# main.net
KiCad netlist of a schematic drawn in Altium Designer
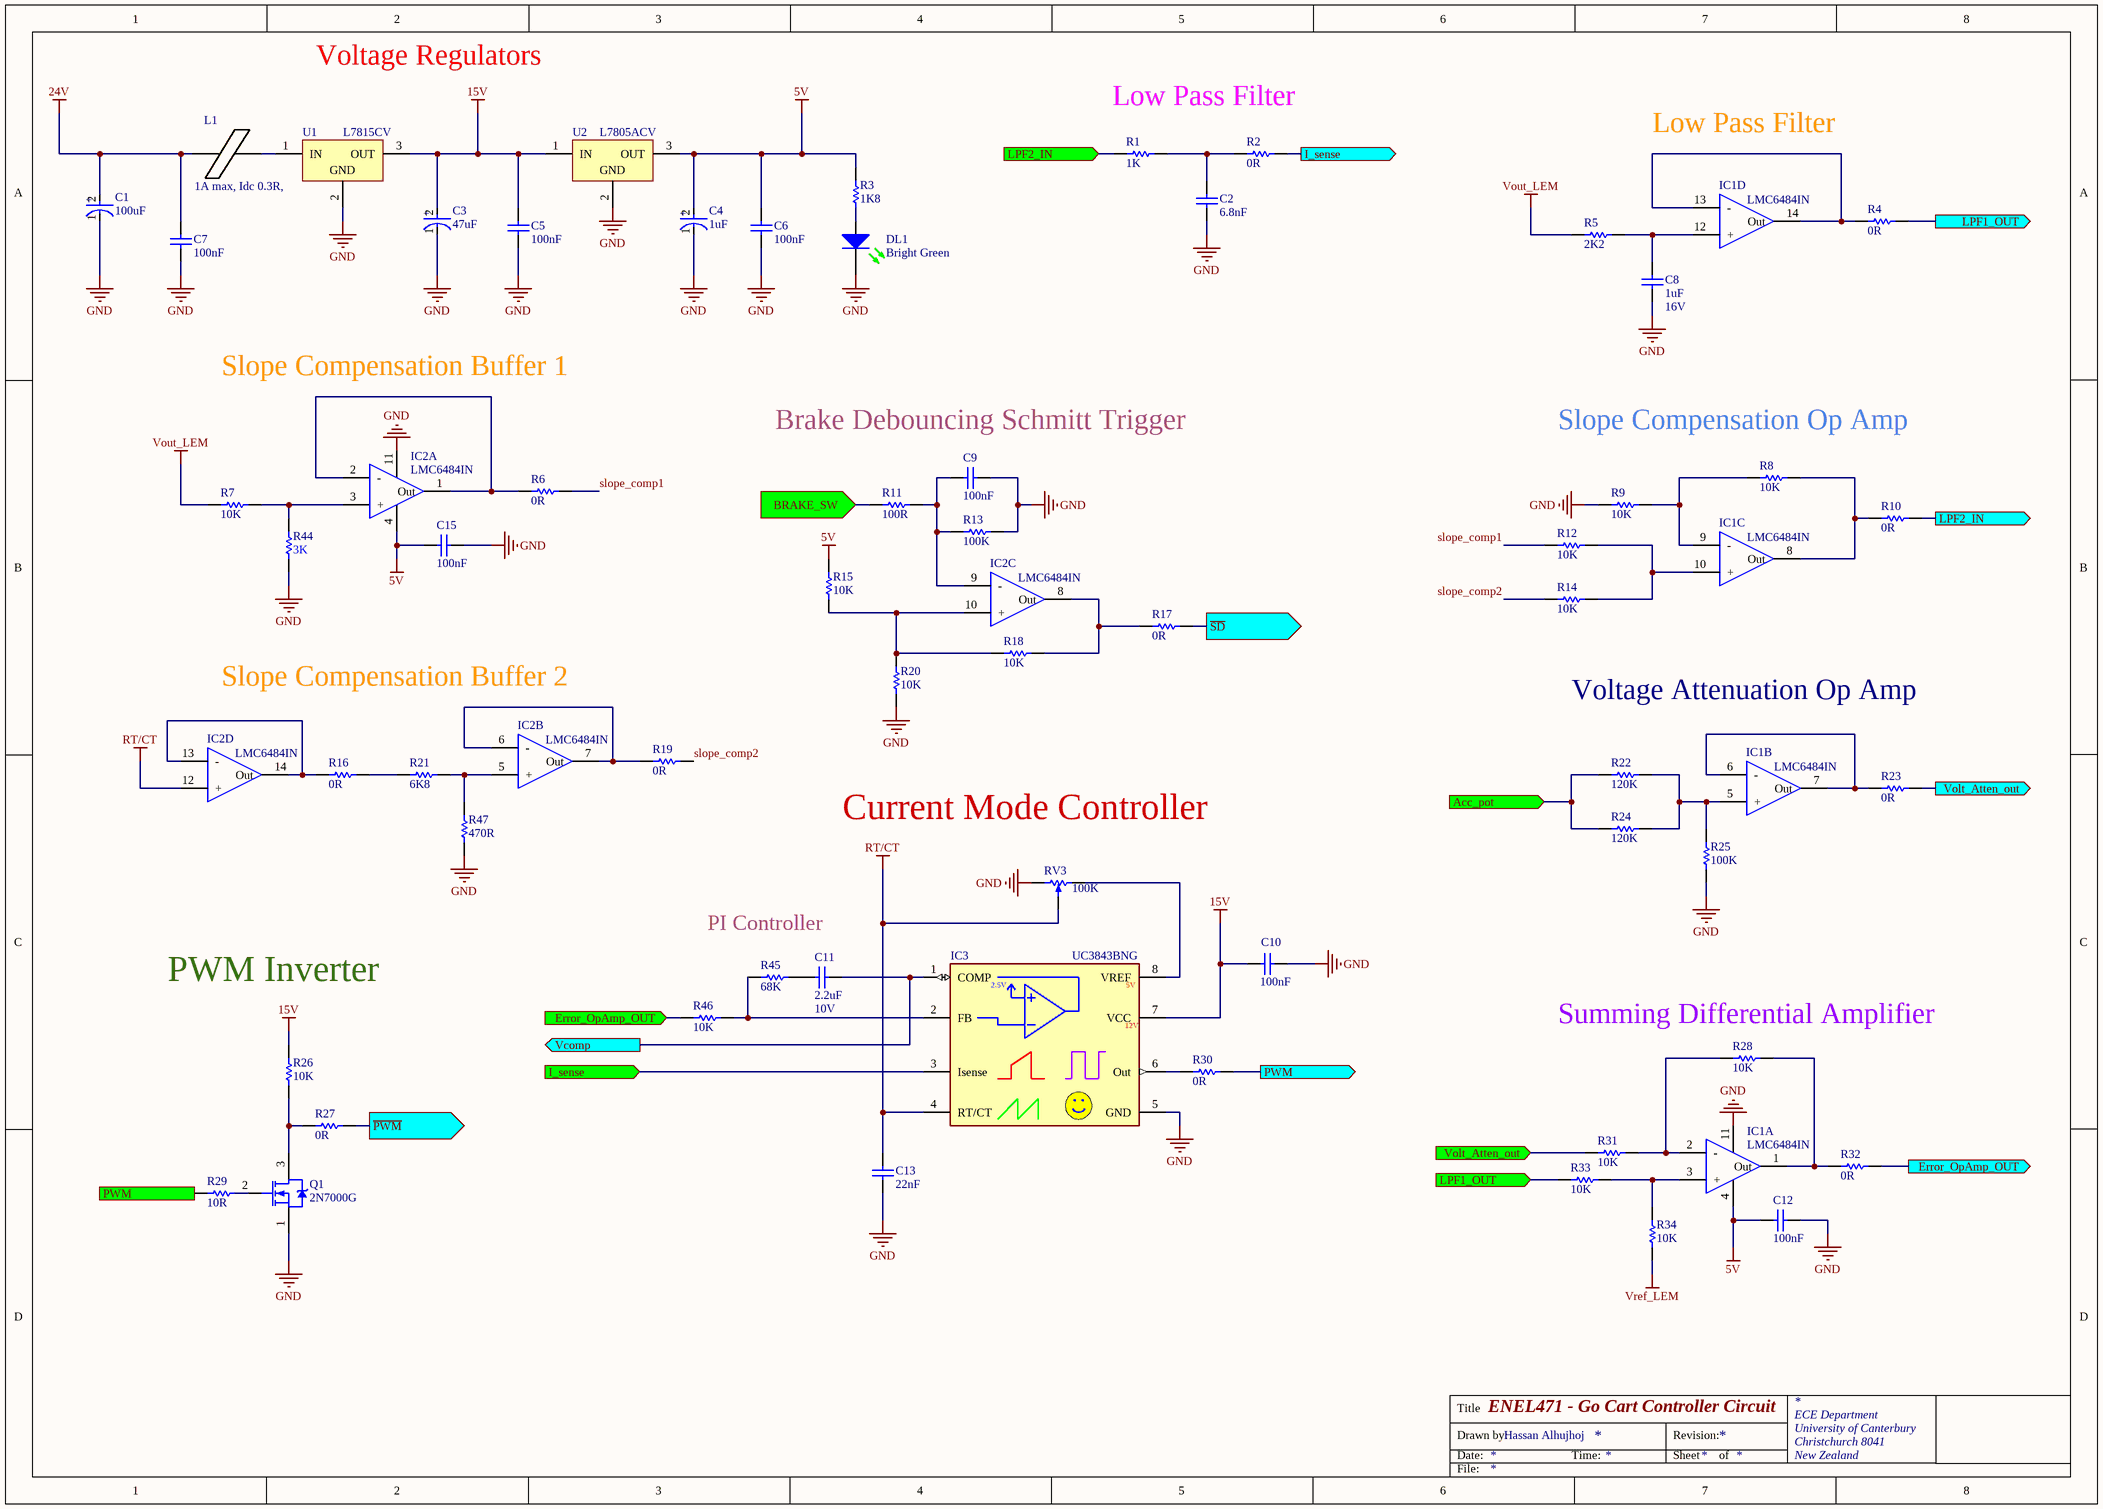
[diagram p0: main.SchDoc]

(export (version "E")
  (design (tool "Eeschema 10.0.6"))
  (components
    (comp (ref "C1")
      (value "100uF")
      (footprint "FP-ESLGM-MFG")
      (description "CAP ALUM 100UF 20% 50V THRU HOLE. Part Number: ESL107M050AGMAA. Dia: 8mm.")
      (fields
        (field (name "TOLERANCE") "20%")
        (field (name "OCTOPART") "https://octopart.com/esl107m050agmaa-kemet-84758890")
      )
      (libsource (lib "Altium Content Vault") (part "a00bbbee19879c290e62620ae7e47b1"))
    )
    (comp (ref "C2")
      (value "6.8nF")
      (footprint "CAPC1608L")
      (description "CAP CER 6.8nF X7R +-10% 50V 0603")
      (libsource (lib "ECE AD19Components_19V1") (part "CC_6.8nF_0603"))
    )
    (comp (ref "C3")
      (value "47uF")
      (footprint "FP-ESLE3-MFG")
      (description "CAP ALUM 10UF 20% 100V THRU HOLE. Part Number: ESL106M100AE3AA. Dia: 6.3mm.")
      (fields (field (name "TOLERANCE") "20%") (field (name "MANUFACTURER PART NUMBER") "ESL106M100AE3AA"))
      (libsource (lib "Altium Content Vault") (part "cf48714ba7e38822c1575c7ec0b6d1f"))
    )
    (comp (ref "C4")
      (value "1uF")
      (footprint "FP-UPW1E220MDD-MFG")
      (description "CAP ALUM 22UF 20% 25V RADIAL. Part Number: UPW1E220MDD. Dia: 5mm.")
      (fields
        (field (name "OCTOPART") "https://octopart.com/upw1e220mdd-nichicon-202818")
        (field (name "TOLERANCE") "20%")
      )
      (libsource (lib "Altium Content Vault") (part "cf48714ba7e38822c1575c7ec0b6d1f"))
    )
    (comp (ref "C5")
      (value "100nF")
      (footprint "CAPC1608L")
      (description "CAP CER 100nF X7R +-10% 50V 0603")
      (libsource (lib "ECE AD19Components_19V1") (part "CC_100nF_0603"))
    )
    (comp (ref "C6")
      (value "100nF")
      (footprint "CAPC1608L")
      (description "CAP CER 100nF X7R +-10% 50V 0603")
      (libsource (lib "ECE AD19Components_19V1") (part "CC_100nF_0603"))
    )
    (comp (ref "C7")
      (value "100nF")
      (footprint "CAPC1608L")
      (description "CAP CER 100nF X7R +-10% 50V 0603")
      (libsource (lib "ECE AD19Components_19V1") (part "CC_100nF_0603"))
    )
    (comp (ref "C8")
      (value "1uF")
      (footprint "CAPC1608L")
      (description "CAP CER 1uF Y5V -20% +80% 16V 0603")
      (fields (field (name "MAX VOLTAGE") "16V"))
      (libsource (lib "ECE AD19Components_19V1") (part "CC_1uF_0603"))
    )
    (comp (ref "C9")
      (value "100nF")
      (footprint "CAPC1608L")
      (description "CAP CER 100nF X7R +-10% 50V 0603")
      (libsource (lib "ECE AD19Components_19V1") (part "CC_100nF_0603"))
    )
    (comp (ref "C10")
      (value "100nF")
      (footprint "CAPC1608L")
      (description "CAP CER 100nF X7R +-10% 50V 0603")
      (libsource (lib "ECE AD19Components_19V1") (part "CC_100nF_0603"))
    )
    (comp (ref "C11")
      (value "2.2uF")
      (footprint "CAPC1608L")
      (description "CAP CER 2.2uF X5R +-20% 10V 0603")
      (fields (field (name "MAX VOLTAGE") "10V"))
      (libsource (lib "ECE AD19Components_19V1") (part "CC_2.2uF_0603"))
    )
    (comp (ref "C12")
      (value "100nF")
      (footprint "CAPC1608L")
      (description "CAP CER 100nF X7R +-10% 50V 0603")
      (libsource (lib "ECE AD19Components_19V1") (part "CC_100nF_0603"))
    )
    (comp (ref "C13")
      (value "22nF")
      (footprint "CAPC1608L")
      (description "CAP CER 22nF X7R +-10% 50V 0603")
      (libsource (lib "ECE AD19Components_19V1") (part "CC_22nF_0603"))
    )
    (comp (ref "C15")
      (value "100nF")
      (footprint "CAPC1608L")
      (description "CAP CER 100nF X7R +-10% 50V 0603")
      (libsource (lib "ECE AD19Components_19V1") (part "CC_100nF_0603"))
    )
    (comp (ref "DL1")
      (value "Bright Green")
      (footprint "WL-SMCW0603")
      (description "LED Bright Green 40mcd 0603 SMD")
      (fields
        (field (name "MANUFACTURER") "WURTH ELEKTRONIK")
        (field (name "MANUFACTURER PART NUMBER") "150060VS75000")
        (field (name "LED COLOUR") "Bright Green")
      )
      (libsource (lib "ECE AD19Components_19V1") (part "DL_150060VS75000"))
    )
    (comp (ref "IC1")
      (value "LMC6484IN")
      (footprint "SamacSys:DIP794W56P254L1905H533Q14N")
      (description "Integrated Circuit")
      (fields (field (name "MOUSER PART NUMBER") "926-LMC6484IN"))
      (libsource (lib "SamacSys") (part "LMC6484IN"))
    )
    (comp (ref "IC2")
      (value "LMC6484IN")
      (footprint "SamacSys:DIP794W56P254L1905H533Q14N")
      (description "Integrated Circuit")
      (fields (field (name "MOUSER PART NUMBER") "926-LMC6484IN"))
      (libsource (lib "SamacSys") (part "LMC6484IN"))
    )
    (comp (ref "IC3")
      (value "UC3843BNG")
      (footprint "SamacSys:DIP794W56P254L959H533Q8B")
      (description "Integrated Circuit")
      (fields (field (name "MOUSER PART NUMBER") "863-UC3843BNG"))
      (libsource (lib "SamacSys") (part "UC3843BNG"))
    )
    (comp (ref "L1")
      (value "1A max, Idc 0.3R,")
      (footprint "INDC3216L")
      (description "Ferrite Bead, Rdc 0.3R, Z100MHZ 600R, Imax 1A, SMD 1206")
      (fields
        (field (name "MANUFACTURER") "FAIR-RITE")
        (field (name "MANUFACTURER PART NUMBER") "2512066017Y1")
      )
      (libsource (lib "ECE AD19Components_19V1") (part "IN_Ferrite-Bead"))
    )
    (comp (ref "Q1")
      (value "2N7000G")
      (footprint "ONSC-TO-92-3-29-11")
      (description "Small Signal MOSFET, 200 mA, 60 V, N-Channel, 3-Pin TO-92, Pb-Free, Bulk Box")
      (fields (field (name "MANUFACTURER") "On Semiconductor"))
      (libsource (lib "Altium Content Vault") (part "ONSC-NMOS-S1G2D3-3"))
    )
    (comp (ref "R1")
      (value "1K")
      (footprint "RESC1608L")
      (description "RES 1.0K OHM 1/10W 5% 0603 SMD")
      (libsource (lib "ECE AD19Components_19V1") (part "RS_1K"))
    )
    (comp (ref "R2")
      (value "0R")
      (footprint "RESC1608L")
      (description "RES 0.0 OHM 1/10W 5% 0603 SMD")
      (libsource (lib "ECE AD19Components_19V1") (part "RS_0R0"))
    )
    (comp (ref "R3")
      (value "1K8")
      (footprint "RESC1608L")
      (description "RES 1.8K OHM 1/10W 5% 0603 SMD")
      (libsource (lib "ECE AD19Components_19V1") (part "RS_1K8"))
    )
    (comp (ref "R4")
      (value "0R")
      (footprint "RESC1608L")
      (description "RES 0.0 OHM 1/10W 5% 0603 SMD")
      (libsource (lib "ECE AD19Components_19V1") (part "RS_0R0"))
    )
    (comp (ref "R5")
      (value "2K2")
      (footprint "RESC1608L")
      (description "RES 2.2K OHM 1/10W 5% 0603 SMD")
      (libsource (lib "ECE AD19Components_19V1") (part "RS_2K2"))
    )
    (comp (ref "R6")
      (value "0R")
      (footprint "RESC1608L")
      (description "RES 0.0 OHM 1/10W 5% 0603 SMD")
      (libsource (lib "ECE AD19Components_19V1") (part "RS_0R0"))
    )
    (comp (ref "R7")
      (value "10K")
      (footprint "RESC1608L")
      (description "RES 10.0K OHM 1/10W 5% 0603 SMD")
      (libsource (lib "ECE AD19Components_19V1") (part "RS_10K"))
    )
    (comp (ref "R8")
      (value "10K")
      (footprint "RESC1608L")
      (description "RES 10.0K OHM 1/10W 5% 0603 SMD")
      (libsource (lib "ECE AD19Components_19V1") (part "RS_10K"))
    )
    (comp (ref "R9")
      (value "10K")
      (footprint "RESC1608L")
      (description "RES 10.0K OHM 1/10W 5% 0603 SMD")
      (libsource (lib "ECE AD19Components_19V1") (part "RS_10K"))
    )
    (comp (ref "R10")
      (value "0R")
      (footprint "RESC1608L")
      (description "RES 0.0 OHM 1/10W 5% 0603 SMD")
      (libsource (lib "ECE AD19Components_19V1") (part "RS_0R0"))
    )
    (comp (ref "R11")
      (value "100R")
      (footprint "RESC1608L")
      (description "RES 100 OHM 1/10W 5% 0603 SMD")
      (libsource (lib "ECE AD19Components_19V1") (part "RS_100R"))
    )
    (comp (ref "R12")
      (value "10K")
      (footprint "RESC1608L")
      (description "RES 10.0K OHM 1/10W 5% 0603 SMD")
      (libsource (lib "ECE AD19Components_19V1") (part "RS_10K"))
    )
    (comp (ref "R13")
      (value "100K")
      (footprint "RESC1608L")
      (description "RES 100K OHM 1/10W 5% 0603 SMD")
      (libsource (lib "ECE AD19Components_19V1") (part "RS_100K"))
    )
    (comp (ref "R14")
      (value "10K")
      (footprint "RESC1608L")
      (description "RES 10.0K OHM 1/10W 5% 0603 SMD")
      (libsource (lib "ECE AD19Components_19V1") (part "RS_10K"))
    )
    (comp (ref "R15")
      (value "10K")
      (footprint "RESC1608L")
      (description "RES 10.0K OHM 1/10W 5% 0603 SMD")
      (libsource (lib "ECE AD19Components_19V1") (part "RS_10K"))
    )
    (comp (ref "R16")
      (value "0R")
      (footprint "RESC1608L")
      (description "RES 0.0 OHM 1/10W 5% 0603 SMD")
      (libsource (lib "ECE AD19Components_19V1") (part "RS_0R0"))
    )
    (comp (ref "R17")
      (value "0R")
      (footprint "RESC1608L")
      (description "RES 0.0 OHM 1/10W 5% 0603 SMD")
      (libsource (lib "ECE AD19Components_19V1") (part "RS_0R0"))
    )
    (comp (ref "R18")
      (value "10K")
      (footprint "RESC1608L")
      (description "RES 10.0K OHM 1/10W 5% 0603 SMD")
      (libsource (lib "ECE AD19Components_19V1") (part "RS_10K"))
    )
    (comp (ref "R19")
      (value "0R")
      (footprint "RESC1608L")
      (description "RES 0.0 OHM 1/10W 5% 0603 SMD")
      (libsource (lib "ECE AD19Components_19V1") (part "RS_0R0"))
    )
    (comp (ref "R20")
      (value "10K")
      (footprint "RESC1608L")
      (description "RES 10.0K OHM 1/10W 5% 0603 SMD")
      (libsource (lib "ECE AD19Components_19V1") (part "RS_10K"))
    )
    (comp (ref "R21")
      (value "6K8")
      (footprint "RESC1608L")
      (description "RES 6k8 OHM 1/10W 5% 0603 SMD")
      (libsource (lib "ECE AD19Components_19V1") (part "RS_6K8"))
    )
    (comp (ref "R22")
      (value "120K")
      (footprint "RESC1608L")
      (description "RES 120K OHM 1/10W 5% 0603 SMD")
      (libsource (lib "ECE AD19Components_19V1") (part "RS_120K"))
    )
    (comp (ref "R23")
      (value "0R")
      (footprint "RESC1608L")
      (description "RES 0.0 OHM 1/10W 5% 0603 SMD")
      (libsource (lib "ECE AD19Components_19V1") (part "RS_0R0"))
    )
    (comp (ref "R24")
      (value "120K")
      (footprint "RESC1608L")
      (description "RES 120K OHM 1/10W 5% 0603 SMD")
      (libsource (lib "ECE AD19Components_19V1") (part "RS_120K"))
    )
    (comp (ref "R25")
      (value "100K")
      (footprint "RESC1608L")
      (description "RES 100K OHM 1/10W 5% 0603 SMD")
      (libsource (lib "ECE AD19Components_19V1") (part "RS_100K"))
    )
    (comp (ref "R26")
      (value "10K")
      (footprint "RESC1608L")
      (description "RES 10.0K OHM 1/10W 5% 0603 SMD")
      (libsource (lib "ECE AD19Components_19V1") (part "RS_10K"))
    )
    (comp (ref "R27")
      (value "0R")
      (footprint "RESC1608L")
      (description "RES 0.0 OHM 1/10W 5% 0603 SMD")
      (libsource (lib "ECE AD19Components_19V1") (part "RS_0R0"))
    )
    (comp (ref "R28")
      (value "10K")
      (footprint "RESC1608L")
      (description "RES 10.0K OHM 1/10W 5% 0603 SMD")
      (libsource (lib "ECE AD19Components_19V1") (part "RS_10K"))
    )
    (comp (ref "R29")
      (value "10R")
      (footprint "RESC1608L")
      (description "RES 10 OHM 1/10W 5% 0603 SMD")
      (libsource (lib "ECE AD19Components_19V1") (part "RS_10R"))
    )
    (comp (ref "R30")
      (value "0R")
      (footprint "RESC1608L")
      (description "RES 0.0 OHM 1/10W 5% 0603 SMD")
      (libsource (lib "ECE AD19Components_19V1") (part "RS_0R0"))
    )
    (comp (ref "R31")
      (value "10K")
      (footprint "RESC1608L")
      (description "RES 10.0K OHM 1/10W 5% 0603 SMD")
      (libsource (lib "ECE AD19Components_19V1") (part "RS_10K"))
    )
    (comp (ref "R32")
      (value "0R")
      (footprint "RESC1608L")
      (description "RES 0.0 OHM 1/10W 5% 0603 SMD")
      (libsource (lib "ECE AD19Components_19V1") (part "RS_0R0"))
    )
    (comp (ref "R33")
      (value "10K")
      (footprint "RESC1608L")
      (description "RES 10.0K OHM 1/10W 5% 0603 SMD")
      (libsource (lib "ECE AD19Components_19V1") (part "RS_10K"))
    )
    (comp (ref "R34")
      (value "10K")
      (footprint "RESC1608L")
      (description "RES 10.0K OHM 1/10W 5% 0603 SMD")
      (libsource (lib "ECE AD19Components_19V1") (part "RS_10K"))
    )
    (comp (ref "R44")
      (value "3K")
      (footprint "RESC1608L")
      (description "RES 3K OHM 1/10W 5% 0603 SMD")
      (libsource (lib "ECE AD19Components_19V1") (part "RS_3K"))
    )
    (comp (ref "R45")
      (value "68K")
      (footprint "RESC1608L")
      (description "RES 68.0K OHM 1/10W 5% 0603 SMD")
      (libsource (lib "ECE AD19Components_19V1") (part "RS_68K"))
    )
    (comp (ref "R46")
      (value "10K")
      (footprint "RESC1608L")
      (description "RES 10.0K OHM 1/10W 5% 0603 SMD")
      (libsource (lib "ECE AD19Components_19V1") (part "RS_10K"))
    )
    (comp (ref "R47")
      (value "470R")
      (footprint "RESC1608L")
      (description "RES 470 OHM 1/10W 5% 0603 SMD")
      (libsource (lib "ECE AD19Components_19V1") (part "RS_470R"))
    )
    (comp (ref "RV3")
      (value "100K")
      (footprint "PVZ2A")
      (description "Trim Pot SMD 100K Murata PVZ2 Series SMD")
      (fields
        (field (name "MANUFACTURER") "MURATA")
        (field (name "MANUFACTURER PART NUMBER") "PVZ2A104C04B00")
      )
      (libsource (lib "ECE AD19Components_19V1") (part "RM_100K"))
    )
    (comp (ref "U1")
      (value "L7815CV")
      (footprint "TO220")
      (description "Positive Voltage Regulator, 15V, 3-Pin TO-220")
      (libsource (lib "Altium Content Vault") (part "PM-REG-L4940-SIL3"))
    )
    (comp (ref "U2")
      (value "L7805ACV")
      (footprint "TO220")
      (description "Positive Voltage Regulator, 5V, 3-Pin TO-220")
      (libsource (lib "Altium Content Vault") (part "PM-REG-L4940-SIL3"))
    )
  )
  (nets
    (net (code "1") (name "/Acc_pot") (class "Default")
      (node (ref "R22") (pin "2") (pinfunction "2_2") (pintype "passive"))
      (node (ref "R24") (pin "1") (pinfunction "1_1") (pintype "passive"))
    )
    (net (code "2") (name "/BRAKE_SW") (class "Default")
      (node (ref "R11") (pin "1") (pinfunction "1_1") (pintype "passive"))
    )
    (net (code "3") (name "/Error_OpAmp_OUT") (class "Default")
      (node (ref "R32") (pin "2") (pinfunction "2_2") (pintype "passive"))
      (node (ref "R46") (pin "1") (pinfunction "1_1") (pintype "passive"))
    )
    (net (code "4") (name "/I_sense") (class "Default")
      (node (ref "IC3") (pin "3") (pinfunction "Isense_3") (pintype "passive"))
      (node (ref "R2") (pin "2") (pinfunction "2_2") (pintype "passive"))
    )
    (net (code "5") (name "/LPF1_OUT") (class "Default")
      (node (ref "R33") (pin "1") (pinfunction "1_1") (pintype "passive"))
      (node (ref "R4") (pin "2") (pinfunction "2_2") (pintype "passive"))
    )
    (net (code "6") (name "/LPF2_IN") (class "Default")
      (node (ref "R1") (pin "1") (pinfunction "1_1") (pintype "passive"))
      (node (ref "R10") (pin "2") (pinfunction "2_2") (pintype "passive"))
    )
    (net (code "7") (name "/PWM") (class "Default")
      (node (ref "R29") (pin "1") (pinfunction "1_1") (pintype "passive"))
      (node (ref "R30") (pin "2") (pinfunction "2_2") (pintype "passive"))
    )
    (net (code "8") (name "/Vcomp") (class "Default")
      (node (ref "C11") (pin "1") (pinfunction "1_1") (pintype "passive"))
      (node (ref "IC3") (pin "1") (pinfunction "COMP_1") (pintype "bidirectional"))
    )
    (net (code "9") (name "/Volt_Atten_out") (class "Default")
      (node (ref "R23") (pin "2") (pinfunction "2_2") (pintype "passive"))
      (node (ref "R31") (pin "1") (pinfunction "1_1") (pintype "passive"))
    )
    (net (code "10") (name "/slope_comp1") (class "Default")
      (node (ref "R12") (pin "1") (pinfunction "1_1") (pintype "passive"))
      (node (ref "R6") (pin "2") (pinfunction "2_2") (pintype "passive"))
    )
    (net (code "11") (name "/slope_comp2") (class "Default")
      (node (ref "R14") (pin "1") (pinfunction "1_1") (pintype "passive"))
      (node (ref "R19") (pin "2") (pinfunction "2_2") (pintype "passive"))
    )
    (net (code "12") (name "/~{PWM}") (class "Default")
      (node (ref "R27") (pin "2") (pinfunction "2_2") (pintype "passive"))
    )
    (net (code "13") (name "/~{SD}") (class "Default")
      (node (ref "R17") (pin "2") (pinfunction "2_2") (pintype "passive"))
    )
    (net (code "14") (name "5V") (class "Default")
      (node (ref "C12") (pin "1") (pinfunction "1_1") (pintype "passive"))
      (node (ref "C15") (pin "1") (pinfunction "1_1") (pintype "passive"))
      (node (ref "C4") (pin "2") (pinfunction "A_2") (pintype "passive"))
      (node (ref "C6") (pin "1") (pinfunction "1_1") (pintype "passive"))
      (node (ref "IC1") (pin "4") (pinfunction "Vcc_4") (pintype "power_in"))
      (node (ref "IC2") (pin "4") (pinfunction "Vcc_4") (pintype "power_in"))
      (node (ref "R15") (pin "2") (pinfunction "2_2") (pintype "passive"))
      (node (ref "R3") (pin "1") (pinfunction "1_1") (pintype "passive"))
      (node (ref "U2") (pin "3") (pinfunction "OUT_3") (pintype "power_in"))
    )
    (net (code "15") (name "15V") (class "Default")
      (node (ref "C10") (pin "1") (pinfunction "1_1") (pintype "passive"))
      (node (ref "C3") (pin "2") (pinfunction "A_2") (pintype "passive"))
      (node (ref "C5") (pin "1") (pinfunction "1_1") (pintype "passive"))
      (node (ref "IC3") (pin "7") (pinfunction "VCC_7") (pintype "power_in"))
      (node (ref "R26") (pin "2") (pinfunction "2_2") (pintype "passive"))
      (node (ref "U1") (pin "3") (pinfunction "OUT_3") (pintype "power_in"))
      (node (ref "U2") (pin "1") (pinfunction "IN_1") (pintype "power_in"))
    )
    (net (code "16") (name "24V") (class "Default")
      (node (ref "C1") (pin "2") (pinfunction "A_2") (pintype "passive"))
      (node (ref "C7") (pin "1") (pinfunction "1_1") (pintype "passive"))
      (node (ref "L1") (pin "1") (pinfunction "1_1") (pintype "passive"))
    )
    (net (code "17") (name "GND") (class "Default")
      (node (ref "C1") (pin "1") (pinfunction "C_1") (pintype "passive"))
      (node (ref "C10") (pin "2") (pinfunction "2_2") (pintype "passive"))
      (node (ref "C12") (pin "2") (pinfunction "2_2") (pintype "passive"))
      (node (ref "C13") (pin "2") (pinfunction "2_2") (pintype "passive"))
      (node (ref "C15") (pin "2") (pinfunction "2_2") (pintype "passive"))
      (node (ref "C2") (pin "1") (pinfunction "1_1") (pintype "passive"))
      (node (ref "C3") (pin "1") (pinfunction "C_1") (pintype "passive"))
      (node (ref "C4") (pin "1") (pinfunction "C_1") (pintype "passive"))
      (node (ref "C5") (pin "2") (pinfunction "2_2") (pintype "passive"))
      (node (ref "C6") (pin "2") (pinfunction "2_2") (pintype "passive"))
      (node (ref "C7") (pin "2") (pinfunction "2_2") (pintype "passive"))
      (node (ref "C8") (pin "1") (pinfunction "1_1") (pintype "passive"))
      (node (ref "C9") (pin "2") (pinfunction "2_2") (pintype "passive"))
      (node (ref "DL1") (pin "1") (pinfunction "K_1") (pintype "passive"))
      (node (ref "IC1") (pin "11") (pinfunction "-Vcc_11") (pintype "power_in"))
      (node (ref "IC2") (pin "11") (pinfunction "-Vcc_11") (pintype "power_in"))
      (node (ref "IC3") (pin "5") (pinfunction "GND_5") (pintype "power_in"))
      (node (ref "Q1") (pin "1") (pinfunction "S_1") (pintype "passive"))
      (node (ref "R13") (pin "2") (pinfunction "2_2") (pintype "passive"))
      (node (ref "R20") (pin "1") (pinfunction "1_1") (pintype "passive"))
      (node (ref "R25") (pin "1") (pinfunction "1_1") (pintype "passive"))
      (node (ref "R44") (pin "1") (pinfunction "1_1") (pintype "passive"))
      (node (ref "R47") (pin "1") (pinfunction "1_1") (pintype "passive"))
      (node (ref "R9") (pin "1") (pinfunction "1_1") (pintype "passive"))
      (node (ref "RV3") (pin "3") (pinfunction "-_3") (pintype "passive"))
      (node (ref "U1") (pin "2") (pinfunction "GND_2") (pintype "power_in"))
      (node (ref "U2") (pin "2") (pinfunction "GND_2") (pintype "power_in"))
    )
    (net (code "18") (name "Net-(C2-Pad2)") (class "Default")
      (node (ref "C2") (pin "2") (pinfunction "2_2") (pintype "passive"))
      (node (ref "R1") (pin "2") (pinfunction "2_2") (pintype "passive"))
      (node (ref "R2") (pin "1") (pinfunction "1_1") (pintype "passive"))
    )
    (net (code "19") (name "Net-(C11-Pad2)") (class "Default")
      (node (ref "C11") (pin "2") (pinfunction "2_2") (pintype "passive"))
      (node (ref "R45") (pin "2") (pinfunction "2_2") (pintype "passive"))
    )
    (net (code "20") (name "Net-(DL1-A)") (class "Default")
      (node (ref "DL1") (pin "2") (pinfunction "A_2") (pintype "passive"))
      (node (ref "R3") (pin "2") (pinfunction "2_2") (pintype "passive"))
    )
    (net (code "21") (name "Net-(IC1A-+)") (class "Default")
      (node (ref "IC1") (pin "3") (pinfunction "+_3") (pintype "passive"))
      (node (ref "R33") (pin "2") (pinfunction "2_2") (pintype "passive"))
      (node (ref "R34") (pin "2") (pinfunction "2_2") (pintype "passive"))
    )
    (net (code "22") (name "Net-(IC1A--)") (class "Default")
      (node (ref "IC1") (pin "2") (pinfunction "-_2") (pintype "passive"))
      (node (ref "R28") (pin "1") (pinfunction "1_1") (pintype "passive"))
      (node (ref "R31") (pin "2") (pinfunction "2_2") (pintype "passive"))
    )
    (net (code "23") (name "Net-(IC1A-Out)") (class "Default")
      (node (ref "IC1") (pin "1") (pinfunction "Out_1") (pintype "passive"))
      (node (ref "R28") (pin "2") (pinfunction "2_2") (pintype "passive"))
      (node (ref "R32") (pin "1") (pinfunction "1_1") (pintype "passive"))
    )
    (net (code "24") (name "Net-(IC1B-+)") (class "Default")
      (node (ref "IC1") (pin "5") (pinfunction "+_5") (pintype "passive"))
      (node (ref "R22") (pin "1") (pinfunction "1_1") (pintype "passive"))
      (node (ref "R24") (pin "2") (pinfunction "2_2") (pintype "passive"))
      (node (ref "R25") (pin "2") (pinfunction "2_2") (pintype "passive"))
    )
    (net (code "25") (name "Net-(IC1B--)") (class "Default")
      (node (ref "IC1") (pin "6") (pinfunction "-_6") (pintype "passive"))
      (node (ref "IC1") (pin "7") (pinfunction "Out_7") (pintype "passive"))
      (node (ref "R23") (pin "1") (pinfunction "1_1") (pintype "passive"))
    )
    (net (code "26") (name "Net-(IC1C-+)") (class "Default")
      (node (ref "IC1") (pin "10") (pinfunction "+_10") (pintype "passive"))
      (node (ref "R12") (pin "2") (pinfunction "2_2") (pintype "passive"))
      (node (ref "R14") (pin "2") (pinfunction "2_2") (pintype "passive"))
    )
    (net (code "27") (name "Net-(IC1C--)") (class "Default")
      (node (ref "IC1") (pin "9") (pinfunction "-_9") (pintype "passive"))
      (node (ref "R8") (pin "1") (pinfunction "1_1") (pintype "passive"))
      (node (ref "R9") (pin "2") (pinfunction "2_2") (pintype "passive"))
    )
    (net (code "28") (name "Net-(IC1C-Out)") (class "Default")
      (node (ref "IC1") (pin "8") (pinfunction "Out_8") (pintype "passive"))
      (node (ref "R10") (pin "1") (pinfunction "1_1") (pintype "passive"))
      (node (ref "R8") (pin "2") (pinfunction "2_2") (pintype "passive"))
    )
    (net (code "29") (name "Net-(IC1D-+)") (class "Default")
      (node (ref "C8") (pin "2") (pinfunction "2_2") (pintype "passive"))
      (node (ref "IC1") (pin "12") (pinfunction "+_12") (pintype "passive"))
      (node (ref "R5") (pin "1") (pinfunction "1_1") (pintype "passive"))
    )
    (net (code "30") (name "Net-(IC1D--)") (class "Default")
      (node (ref "IC1") (pin "13") (pinfunction "-_13") (pintype "passive"))
      (node (ref "IC1") (pin "14") (pinfunction "Out_14") (pintype "passive"))
      (node (ref "R4") (pin "1") (pinfunction "1_1") (pintype "passive"))
    )
    (net (code "31") (name "Net-(IC2A-+)") (class "Default")
      (node (ref "IC2") (pin "3") (pinfunction "+_3") (pintype "passive"))
      (node (ref "R44") (pin "2") (pinfunction "2_2") (pintype "passive"))
      (node (ref "R7") (pin "2") (pinfunction "2_2") (pintype "passive"))
    )
    (net (code "32") (name "Net-(IC2A--)") (class "Default")
      (node (ref "IC2") (pin "1") (pinfunction "Out_1") (pintype "passive"))
      (node (ref "IC2") (pin "2") (pinfunction "-_2") (pintype "passive"))
      (node (ref "R6") (pin "1") (pinfunction "1_1") (pintype "passive"))
    )
    (net (code "33") (name "Net-(IC2B-+)") (class "Default")
      (node (ref "IC2") (pin "5") (pinfunction "+_5") (pintype "passive"))
      (node (ref "R21") (pin "2") (pinfunction "2_2") (pintype "passive"))
      (node (ref "R47") (pin "2") (pinfunction "2_2") (pintype "passive"))
    )
    (net (code "34") (name "Net-(IC2B--)") (class "Default")
      (node (ref "IC2") (pin "6") (pinfunction "-_6") (pintype "passive"))
      (node (ref "IC2") (pin "7") (pinfunction "Out_7") (pintype "passive"))
      (node (ref "R19") (pin "1") (pinfunction "1_1") (pintype "passive"))
    )
    (net (code "35") (name "Net-(IC2C-+)") (class "Default")
      (node (ref "IC2") (pin "10") (pinfunction "+_10") (pintype "passive"))
      (node (ref "R15") (pin "1") (pinfunction "1_1") (pintype "passive"))
      (node (ref "R18") (pin "1") (pinfunction "1_1") (pintype "passive"))
      (node (ref "R20") (pin "2") (pinfunction "2_2") (pintype "passive"))
    )
    (net (code "36") (name "Net-(IC2C--)") (class "Default")
      (node (ref "C9") (pin "1") (pinfunction "1_1") (pintype "passive"))
      (node (ref "IC2") (pin "9") (pinfunction "-_9") (pintype "passive"))
      (node (ref "R11") (pin "2") (pinfunction "2_2") (pintype "passive"))
      (node (ref "R13") (pin "1") (pinfunction "1_1") (pintype "passive"))
    )
    (net (code "37") (name "Net-(IC2C-Out)") (class "Default")
      (node (ref "IC2") (pin "8") (pinfunction "Out_8") (pintype "passive"))
      (node (ref "R17") (pin "1") (pinfunction "1_1") (pintype "passive"))
      (node (ref "R18") (pin "2") (pinfunction "2_2") (pintype "passive"))
    )
    (net (code "38") (name "Net-(IC2D--)") (class "Default")
      (node (ref "IC2") (pin "13") (pinfunction "-_13") (pintype "passive"))
      (node (ref "IC2") (pin "14") (pinfunction "Out_14") (pintype "passive"))
      (node (ref "R16") (pin "1") (pinfunction "1_1") (pintype "passive"))
    )
    (net (code "39") (name "Net-(IC3-FB)") (class "Default")
      (node (ref "IC3") (pin "2") (pinfunction "FB_2") (pintype "passive"))
      (node (ref "R45") (pin "1") (pinfunction "1_1") (pintype "passive"))
      (node (ref "R46") (pin "2") (pinfunction "2_2") (pintype "passive"))
    )
    (net (code "40") (name "Net-(IC3-Out)") (class "Default")
      (node (ref "IC3") (pin "6") (pinfunction "Out_6") (pintype "output"))
      (node (ref "R30") (pin "1") (pinfunction "1_1") (pintype "passive"))
    )
    (net (code "41") (name "Net-(IC3-VREF)") (class "Default")
      (node (ref "IC3") (pin "8") (pinfunction "VREF_8") (pintype "power_in"))
      (node (ref "RV3") (pin "1") (pinfunction "1_1") (pintype "passive"))
    )
    (net (code "42") (name "Net-(Q1-D)") (class "Default")
      (node (ref "Q1") (pin "3") (pinfunction "D_3") (pintype "passive"))
      (node (ref "R26") (pin "1") (pinfunction "1_1") (pintype "passive"))
      (node (ref "R27") (pin "1") (pinfunction "1_1") (pintype "passive"))
    )
    (net (code "43") (name "Net-(Q1-G)") (class "Default")
      (node (ref "Q1") (pin "2") (pinfunction "G_2") (pintype "passive"))
      (node (ref "R29") (pin "2") (pinfunction "2_2") (pintype "passive"))
    )
    (net (code "44") (name "Net-(R16-Pad2)") (class "Default")
      (node (ref "R16") (pin "2") (pinfunction "2_2") (pintype "passive"))
      (node (ref "R21") (pin "1") (pinfunction "1_1") (pintype "passive"))
    )
    (net (code "45") (name "Net-(U1-IN)") (class "Default")
      (node (ref "L1") (pin "2") (pinfunction "2_2") (pintype "passive"))
      (node (ref "U1") (pin "1") (pinfunction "IN_1") (pintype "power_in"))
    )
    (net (code "46") (name "RT{slash}CT") (class "Default")
      (node (ref "C13") (pin "1") (pinfunction "1_1") (pintype "passive"))
      (node (ref "IC2") (pin "12") (pinfunction "+_12") (pintype "passive"))
      (node (ref "IC3") (pin "4") (pinfunction "RT/CT_4") (pintype "passive"))
      (node (ref "RV3") (pin "2") (pinfunction "W_2") (pintype "passive"))
    )
    (net (code "47") (name "Vout_LEM") (class "Default")
      (node (ref "R5") (pin "2") (pinfunction "2_2") (pintype "passive"))
      (node (ref "R7") (pin "1") (pinfunction "1_1") (pintype "passive"))
    )
    (net (code "48") (name "Vref_LEM") (class "Default")
      (node (ref "R34") (pin "1") (pinfunction "1_1") (pintype "passive"))
    )
  )
)
